# TNY275.net
KiCad netlist of a schematic drawn in Altium Designer
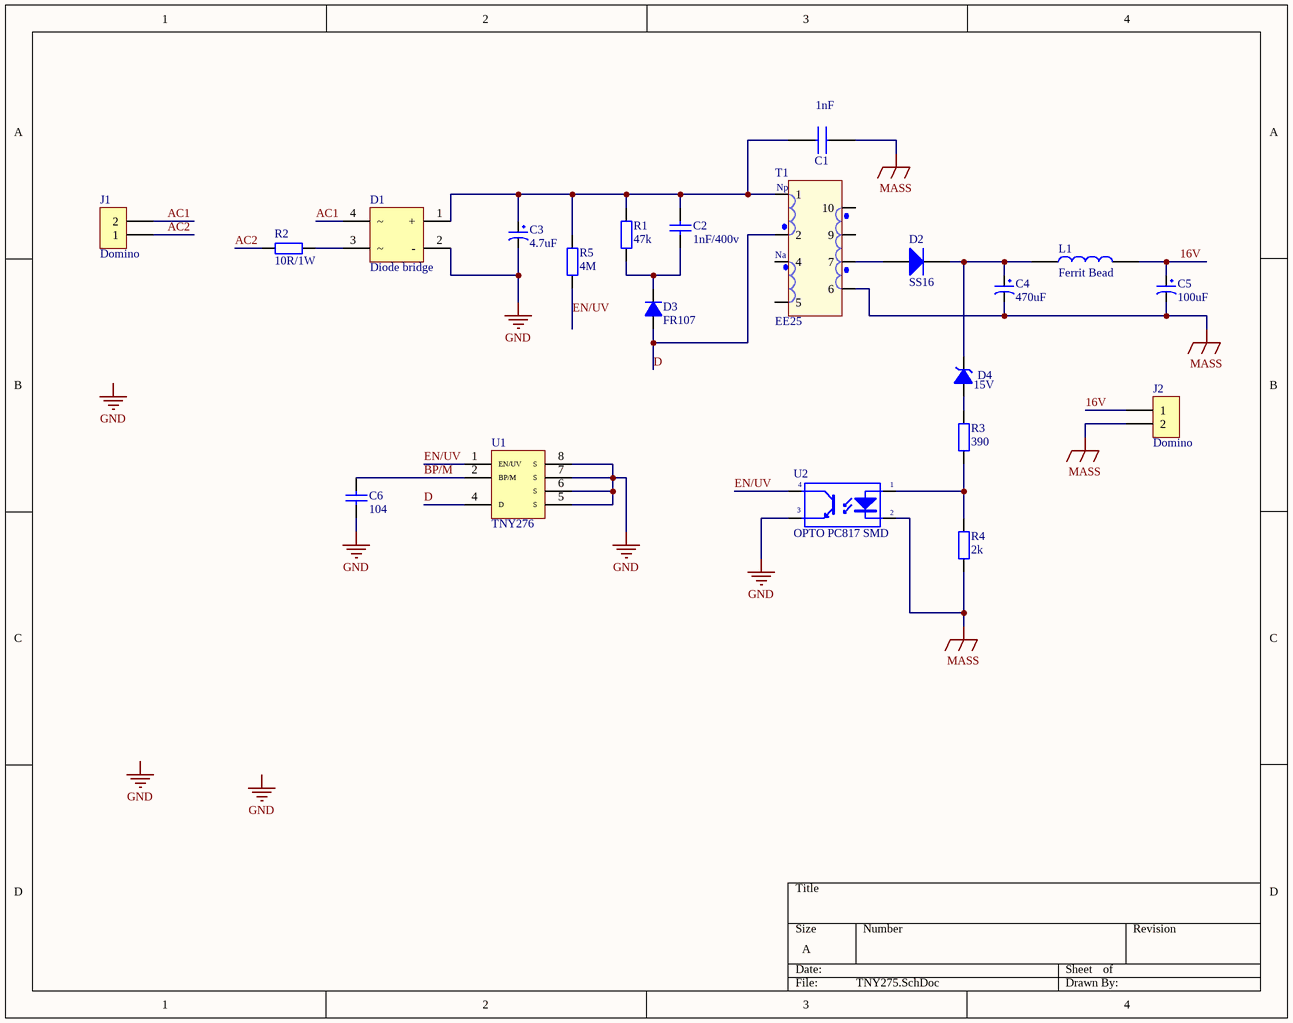
[diagram p0: TNY275.SchDoc]

(export (version "E")
  (design (tool "Eeschema 10.0.6"))
  (components
    (comp (ref "C1")
      (value "1nF")
      (footprint "toan:Tenta capacitor")
      (description "...nF +/-10% 275VAC 15 Through Hole Suppression Capacitors")
      (fields (field (name "MANUFACTURER_PART_NUMBER") "MEX104K275A"))
      (libsource (lib "Tenta capacitor") (part "Tenta capacitor"))
    )
    (comp (ref "C2")
      (value "1nF/400v")
      (footprint "tu tantalum dip5.08")
      (description "tụ cao áp Cắm")
      (libsource (lib "Altium_Lib_by_KhueNguyenCreator") (part "Tu tantalum 10nF DIP5.08"))
    )
    (comp (ref "C3")
      (value "4.7uF")
      (footprint "tu hoa 8mm")
      (description "Cắm")
      (libsource (lib "Altium_Lib_by_KhueNguyenCreator") (part "Tu Hoa 4.7uF 400V 8x12"))
    )
    (comp (ref "C4")
      (value "470uF")
      (footprint "tu hoa 8mm")
      (description "Cắm")
      (libsource (lib "Altium_Lib_by_KhueNguyenCreator") (part "Tu Hoa 470uF 25V 8x13"))
    )
    (comp (ref "C5")
      (value "100uF")
      (footprint "tu hoa 5mm")
      (description "Cắm")
      (libsource (lib "Altium_Lib_by_KhueNguyenCreator") (part "Tu Hoa 100uF 25V 6x11"))
    )
    (comp (ref "C6")
      (value "104")
      (footprint "tu 0805")
      (description "Dán")
      (libsource (lib "Altium_Lib_by_KhueNguyenCreator") (part "Tu 0805 104 50V 10%"))
    )
    (comp (ref "D1")
      (value "Diode bridge")
      (footprint "DS207S:DS207S")
      (description "Diode cau 2A 1000V")
      (libsource (lib "DS207S") (part "DS207S"))
    )
    (comp (ref "D2")
      (value "SS16")
      (footprint "DIODE SMA")
      (description "Dán")
      (libsource (lib "Altium_Lib_by_KhueNguyenCreator") (part "Diode SS14 ( 1N5819)"))
    )
    (comp (ref "D3")
      (value "FR107")
      (footprint "DIODE 2A")
      (description "Cắm")
      (libsource (lib "Altium_Lib_by_KhueNguyenCreator") (part "Diode FR207"))
    )
    (comp (ref "D4")
      (value "15V")
      (footprint "DZ1A")
      (description "Diode Zenner")
      (libsource (lib "syhaunguyen") (part "DZ"))
    )
    (comp (ref "J1")
      (value "Domino")
      (footprint "Domino:Domino")
      (description "Domino 5.04mm")
      (libsource (lib "") (part "Domino_1"))
    )
    (comp (ref "J2")
      (value "Domino")
      (footprint "Domino:Domino")
      (description "Domino 5.04mm")
      (libsource (lib "Domino") (part "Domino"))
    )
    (comp (ref "L1")
      (value "Ferrit Bead")
      (footprint "Cuon Cam:CUON CAM")
      (description "Cuộn lọc RH3.5x9x0.8 Cắm")
      (libsource (lib "Altium_Lib_by_KhueNguyenCreator") (part "CUON CAM 470uH DIP"))
    )
    (comp (ref "R1")
      (value "47k")
      (footprint "tro smd 0805")
      (description "Dán")
      (libsource (lib "Altium_Lib_by_KhueNguyenCreator") (part "Tro 0805 5% 47k"))
    )
    (comp (ref "R2")
      (value "10R/1W")
      (footprint "tro vach 1w")
      (description "Cắm")
      (libsource (lib "Altium_Lib_by_KhueNguyenCreator") (part "Tro Vach 1W 5% 3.3R"))
    )
    (comp (ref "R3")
      (value "390")
      (footprint "tro smd 0805")
      (description "Dán")
      (libsource (lib "Altium_Lib_by_KhueNguyenCreator") (part "Tro 0805 5% 2.2k"))
    )
    (comp (ref "R4")
      (value "2k")
      (footprint "tro smd 0805")
      (description "Dán")
      (libsource (lib "Altium_Lib_by_KhueNguyenCreator") (part "Tro 0805 5% 220R"))
    )
    (comp (ref "R5")
      (value "4M")
      (footprint "tro smd 0805")
      (description "Dán")
      (libsource (lib "Altium_Lib_by_KhueNguyenCreator") (part "Tro 0805 5% 47k"))
    )
    (comp (ref "T1")
      (value "EE25")
      (footprint "toan:EE25_0.5")
      (description "EE25 10PIN")
      (libsource (lib "EE25") (part "EE25"))
    )
    (comp (ref "U1")
      (value "TNY276")
      (footprint "TNY27X DIP:PCBComponent_1")
      (description "TNY274-280\r\nTinySwitch-III Family - DIP/PDIP-8C")
      (libsource (lib "TNY27X-DIP") (part "TNY276"))
    )
    (comp (ref "U2")
      (value "OPTO PC817 SMD")
      (footprint "SOP4")
      (description "Single Opto")
      (libsource (lib "Altium_Lib_by_KhueNguyenCreator") (part "OPTO PC817 SMD"))
    )
  )
  (nets
    (net (code "1") (name "/16V") (class "Default")
      (node (ref "C5") (pin "1") (pinfunction "1_1") (pintype "passive"))
      (node (ref "J2") (pin "1") (pinfunction "1_1") (pintype "passive"))
      (node (ref "L1") (pin "2") (pinfunction "2_2") (pintype "passive"))
    )
    (net (code "2") (name "/AC1") (class "Default")
      (node (ref "D1") (pin "4") (pinfunction "~_4") (pintype "passive"))
      (node (ref "J1") (pin "2") (pinfunction "2_2") (pintype "passive"))
    )
    (net (code "3") (name "/AC2") (class "Default")
      (node (ref "J1") (pin "1") (pinfunction "1_1") (pintype "passive"))
      (node (ref "R2") (pin "1") (pinfunction "1_1") (pintype "passive"))
    )
    (net (code "4") (name "/BP{slash}M") (class "Default")
      (node (ref "C6") (pin "1") (pinfunction "1_1") (pintype "passive"))
      (node (ref "U1") (pin "2") (pinfunction "BP/M_2") (pintype "passive"))
    )
    (net (code "5") (name "/D") (class "Default")
      (node (ref "D3") (pin "1") (pinfunction "A_1") (pintype "passive"))
      (node (ref "T1") (pin "2") (pinfunction "2_2") (pintype "passive"))
      (node (ref "U1") (pin "4") (pinfunction "D_4") (pintype "passive"))
    )
    (net (code "6") (name "/EN{slash}UV") (class "Default")
      (node (ref "R5") (pin "1") (pinfunction "1_1") (pintype "passive"))
      (node (ref "U1") (pin "1") (pinfunction "EN/UV_1") (pintype "passive"))
      (node (ref "U2") (pin "4") (pinfunction "C_4") (pintype "passive"))
    )
    (net (code "7") (name "GND") (class "Default")
      (node (ref "C3") (pin "2") (pinfunction "2_2") (pintype "passive"))
      (node (ref "C6") (pin "2") (pinfunction "2_2") (pintype "passive"))
      (node (ref "D1") (pin "2") (pinfunction "-_2") (pintype "passive"))
      (node (ref "U1") (pin "5") (pinfunction "S_5") (pintype "passive"))
      (node (ref "U1") (pin "6") (pinfunction "S_6") (pintype "passive"))
      (node (ref "U1") (pin "7") (pinfunction "S_7") (pintype "passive"))
      (node (ref "U1") (pin "8") (pinfunction "S_8") (pintype "passive"))
      (node (ref "U2") (pin "3") (pinfunction "E_3") (pintype "passive"))
    )
    (net (code "8") (name "MASS") (class "Default")
      (node (ref "C1") (pin "2") (pinfunction "2_2") (pintype "passive"))
      (node (ref "C4") (pin "2") (pinfunction "2_2") (pintype "passive"))
      (node (ref "C5") (pin "2") (pinfunction "2_2") (pintype "passive"))
      (node (ref "J2") (pin "2") (pinfunction "2_2") (pintype "passive"))
      (node (ref "R4") (pin "1") (pinfunction "1_1") (pintype "passive"))
      (node (ref "T1") (pin "6") (pinfunction "6_6") (pintype "passive"))
      (node (ref "U2") (pin "2") (pinfunction "K_2") (pintype "passive"))
    )
    (net (code "9") (name "Net-(D1-+)") (class "Default")
      (node (ref "C1") (pin "1") (pinfunction "1_1") (pintype "passive"))
      (node (ref "C2") (pin "1") (pinfunction "1_1") (pintype "passive"))
      (node (ref "C3") (pin "1") (pinfunction "1_1") (pintype "passive"))
      (node (ref "D1") (pin "1") (pinfunction "+_1") (pintype "passive"))
      (node (ref "R1") (pin "2") (pinfunction "2_2") (pintype "passive"))
      (node (ref "R5") (pin "2") (pinfunction "2_2") (pintype "passive"))
      (node (ref "T1") (pin "1") (pinfunction "1_1") (pintype "passive"))
    )
    (net (code "10") (name "Net-(D1-~-Pad3)") (class "Default")
      (node (ref "D1") (pin "3") (pinfunction "~_3") (pintype "passive"))
      (node (ref "R2") (pin "2") (pinfunction "2_2") (pintype "passive"))
    )
    (net (code "11") (name "Net-(D2-A)") (class "Default")
      (node (ref "D2") (pin "1") (pinfunction "A_1") (pintype "passive"))
      (node (ref "T1") (pin "7") (pinfunction "7_7") (pintype "passive"))
    )
    (net (code "12") (name "Net-(D2-K)") (class "Default")
      (node (ref "C4") (pin "1") (pinfunction "1_1") (pintype "passive"))
      (node (ref "D2") (pin "2") (pinfunction "K_2") (pintype "passive"))
      (node (ref "D4") (pin "2") (pinfunction "K_2") (pintype "passive"))
      (node (ref "L1") (pin "1") (pinfunction "1_1") (pintype "passive"))
    )
    (net (code "13") (name "Net-(D3-K)") (class "Default")
      (node (ref "C2") (pin "2") (pinfunction "2_2") (pintype "passive"))
      (node (ref "D3") (pin "2") (pinfunction "K_2") (pintype "passive"))
      (node (ref "R1") (pin "1") (pinfunction "1_1") (pintype "passive"))
    )
    (net (code "14") (name "Net-(D4-A)") (class "Default")
      (node (ref "D4") (pin "1") (pinfunction "A_1") (pintype "passive"))
      (node (ref "R3") (pin "2") (pinfunction "2_2") (pintype "passive"))
    )
    (net (code "15") (name "Net-(U2-A)") (class "Default")
      (node (ref "R3") (pin "1") (pinfunction "1_1") (pintype "passive"))
      (node (ref "R4") (pin "2") (pinfunction "2_2") (pintype "passive"))
      (node (ref "U2") (pin "1") (pinfunction "A_1") (pintype "passive"))
    )
    (net (code "16") (name "unconnected-(T1-Pad4)") (class "Default")
      (node (ref "T1") (pin "4") (pinfunction "4_4") (pintype "passive"))
    )
    (net (code "17") (name "unconnected-(T1-Pad5)") (class "Default")
      (node (ref "T1") (pin "5") (pinfunction "5_5") (pintype "passive"))
    )
    (net (code "18") (name "unconnected-(T1-Pad9)") (class "Default")
      (node (ref "T1") (pin "9") (pinfunction "9_9") (pintype "passive"))
    )
    (net (code "19") (name "unconnected-(T1-Pad10)") (class "Default")
      (node (ref "T1") (pin "10") (pinfunction "10_10") (pintype "passive"))
    )
  )
)
